# mini_backplane.net
KiCad netlist of a schematic drawn in Altium Designer
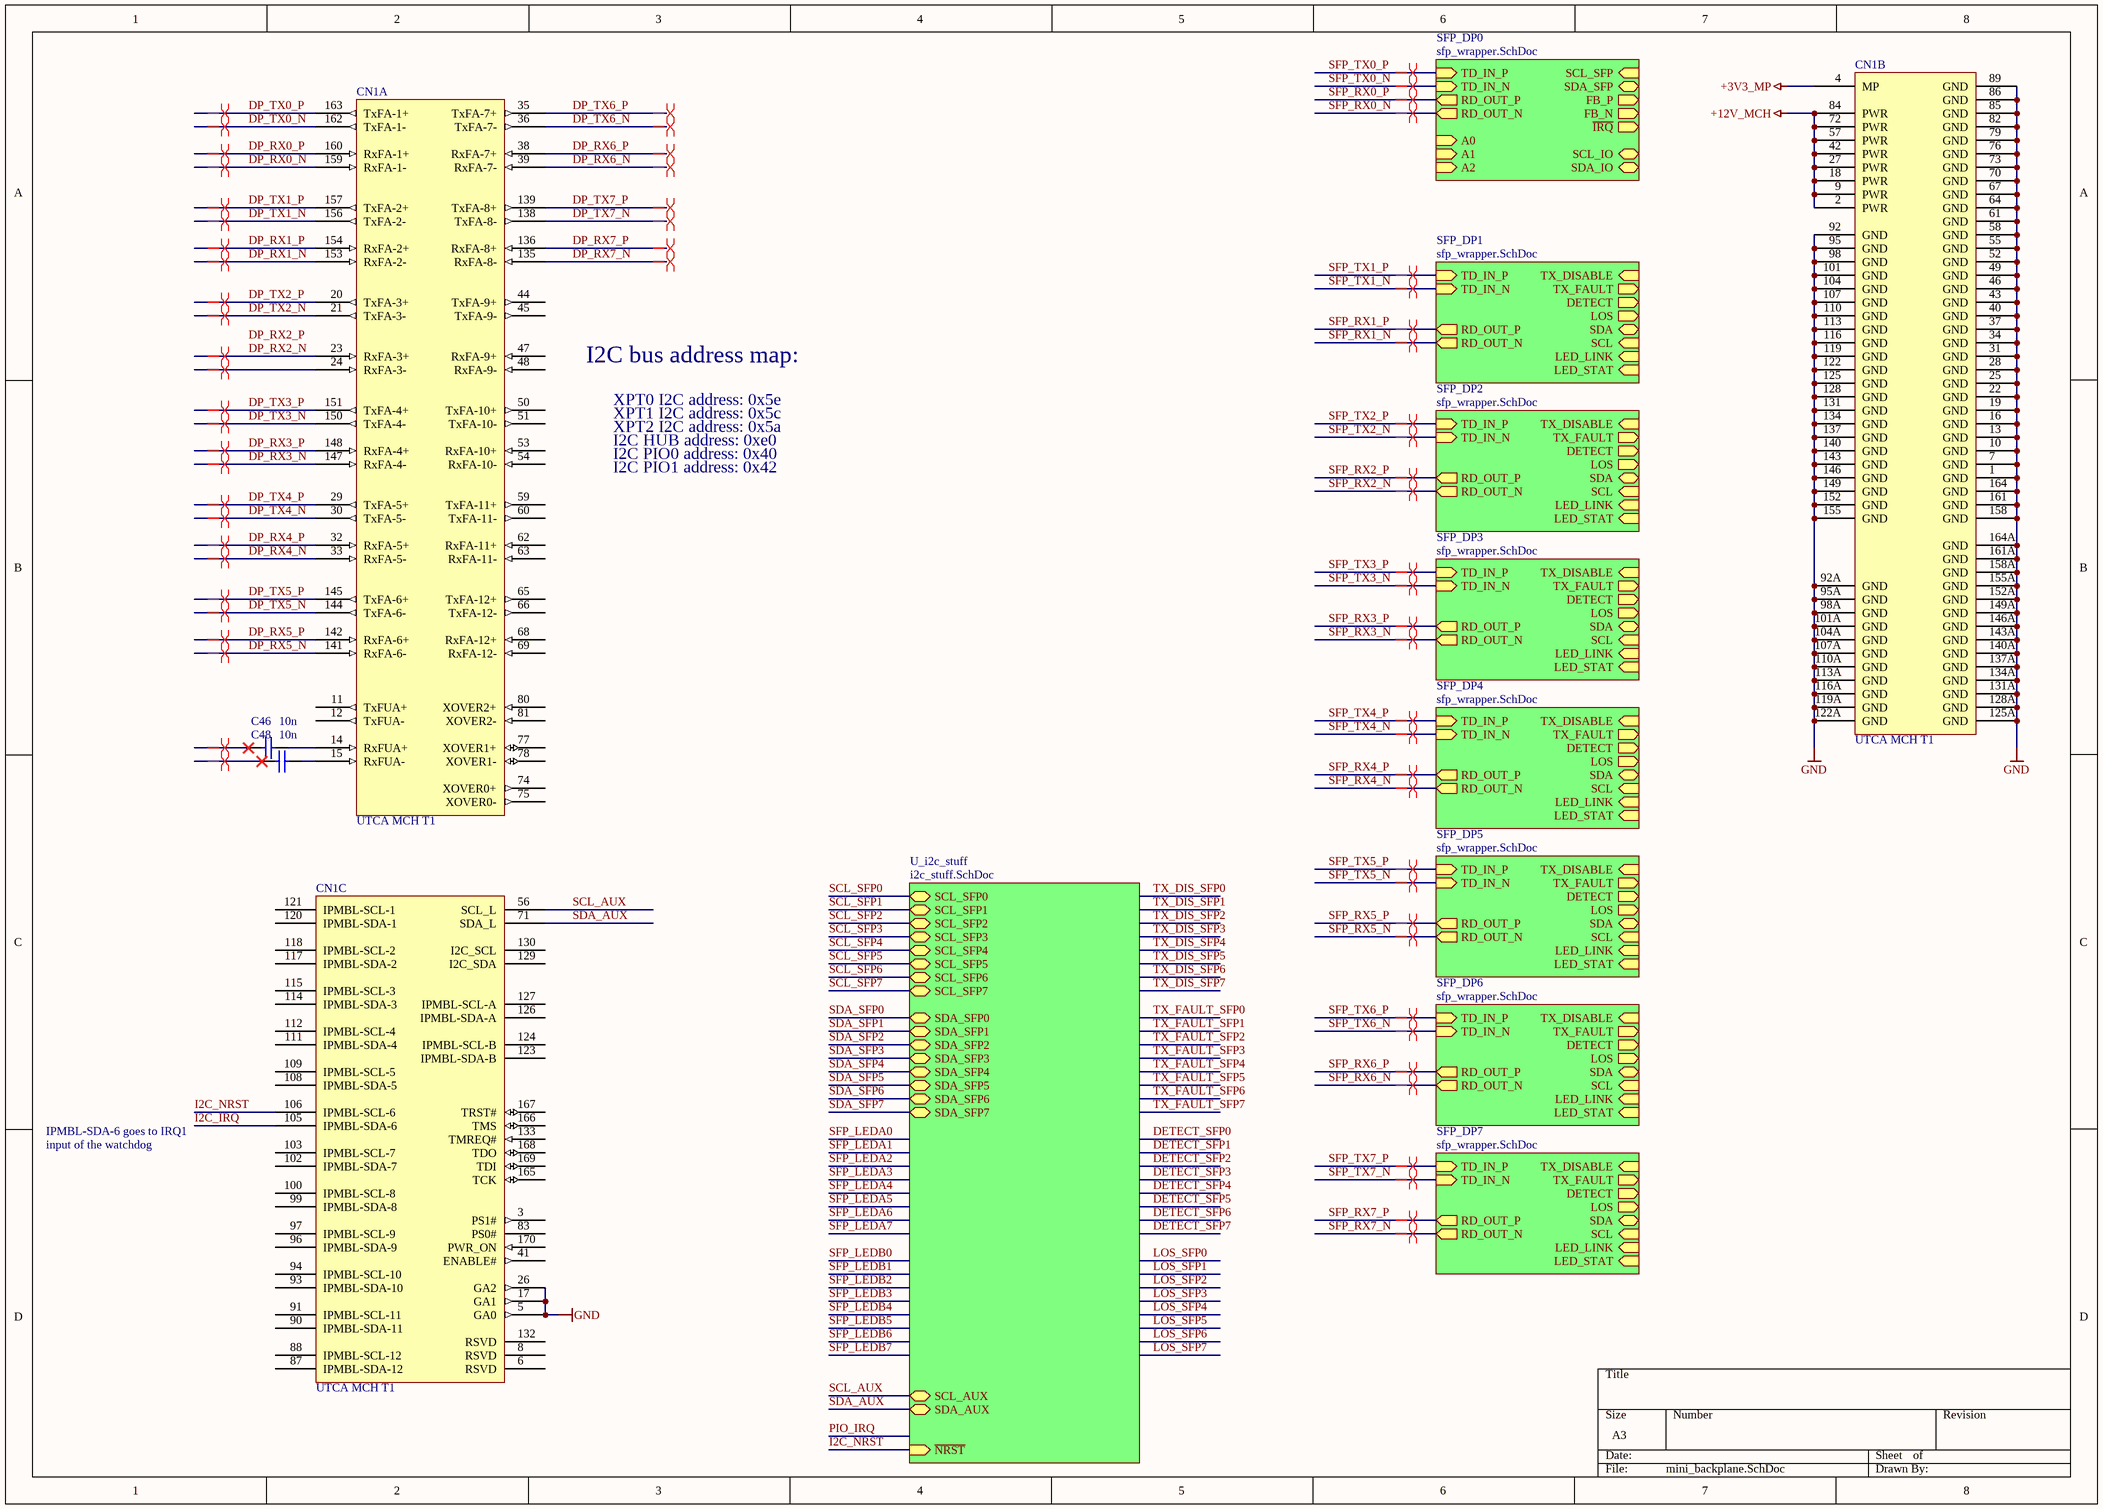
[diagram p0: mini_backplane.SchDoc]

(export (version "E")
  (design (tool "Eeschema 10.0.6"))
  (components
    (comp (ref "C46")
      (value "10n")
      (footprint "CAPC1608X87N")
      (description "Non-polarised capacitor")
      (fields
        (field (name "PART NUMBER") "CC0603_10NF_50V_10%_X7R")
        (field (name "VOLTAGE") "50V")
        (field (name "AUTHOR") "CERN DEM JLC")
      )
      (libsource (lib "Capacitors") (part "Capacitor - non polarized"))
    )
    (comp (ref "C48")
      (value "10n")
      (footprint "CAPC1608X87N")
      (description "Non-polarised capacitor")
      (fields
        (field (name "PART NUMBER") "CC0603_10NF_50V_10%_X7R")
        (field (name "VOLTAGE") "50V")
        (field (name "AUTHOR") "CERN DEM JLC")
      )
      (libsource (lib "Capacitors") (part "Capacitor - non polarized"))
    )
    (comp (ref "CN1")
      (value "UTCA MCH T1")
      (footprint "CON_AMC_MOLEX_75800_00001_REVERSE")
      (description "microTCA MTCA.0  MCH socket (AMC0.0 B+ connector with reversed pins)")
      (libsource (lib "wr_switch") (part "UTCA_MCH_SOCKET"))
    )
  )
  (nets
    (net (code "1") (name "+3V3_MP") (class "Default")
      (node (ref "CN1") (pin "4") (pinfunction "MP_4") (pintype "power_in"))
    )
    (net (code "2") (name "+12V_MCH") (class "Default")
      (node (ref "CN1") (pin "18") (pinfunction "PWR_18") (pintype "power_in"))
      (node (ref "CN1") (pin "2") (pinfunction "PWR_2") (pintype "power_in"))
      (node (ref "CN1") (pin "27") (pinfunction "PWR_27") (pintype "power_in"))
      (node (ref "CN1") (pin "42") (pinfunction "PWR_42") (pintype "power_in"))
      (node (ref "CN1") (pin "57") (pinfunction "PWR_57") (pintype "power_in"))
      (node (ref "CN1") (pin "72") (pinfunction "PWR_72") (pintype "power_in"))
      (node (ref "CN1") (pin "84") (pinfunction "PWR_84") (pintype "power_in"))
      (node (ref "CN1") (pin "9") (pinfunction "PWR_9") (pintype "power_in"))
    )
    (net (code "21") (name "/DP_RX0_N") (class "Default")
      (node (ref "CN1") (pin "159") (pinfunction "RxFA-1-_159") (pintype "input"))
    )
    (net (code "22") (name "/DP_RX0_P") (class "Default")
      (node (ref "CN1") (pin "160") (pinfunction "RxFA-1+_160") (pintype "input"))
    )
    (net (code "23") (name "/DP_RX1_N") (class "Default")
      (node (ref "CN1") (pin "153") (pinfunction "RxFA-2-_153") (pintype "input"))
    )
    (net (code "24") (name "/DP_RX1_P") (class "Default")
      (node (ref "CN1") (pin "154") (pinfunction "RxFA-2+_154") (pintype "input"))
    )
    (net (code "25") (name "/DP_RX2_N") (class "Default")
      (node (ref "CN1") (pin "23") (pinfunction "RxFA-3+_23") (pintype "input"))
    )
    (net (code "27") (name "/DP_RX3_N") (class "Default")
      (node (ref "CN1") (pin "147") (pinfunction "RxFA-4-_147") (pintype "input"))
    )
    (net (code "28") (name "/DP_RX3_P") (class "Default")
      (node (ref "CN1") (pin "148") (pinfunction "RxFA-4+_148") (pintype "input"))
    )
    (net (code "29") (name "/DP_RX4_N") (class "Default")
      (node (ref "CN1") (pin "33") (pinfunction "RxFA-5-_33") (pintype "input"))
    )
    (net (code "30") (name "/DP_RX4_P") (class "Default")
      (node (ref "CN1") (pin "32") (pinfunction "RxFA-5+_32") (pintype "input"))
    )
    (net (code "31") (name "/DP_RX5_N") (class "Default")
      (node (ref "CN1") (pin "141") (pinfunction "RxFA-6-_141") (pintype "input"))
    )
    (net (code "32") (name "/DP_RX5_P") (class "Default")
      (node (ref "CN1") (pin "142") (pinfunction "RxFA-6+_142") (pintype "input"))
    )
    (net (code "33") (name "/DP_RX6_N") (class "Default")
      (node (ref "CN1") (pin "39") (pinfunction "RxFA-7-_39") (pintype "input"))
    )
    (net (code "34") (name "/DP_RX6_P") (class "Default")
      (node (ref "CN1") (pin "38") (pinfunction "RxFA-7+_38") (pintype "input"))
    )
    (net (code "35") (name "/DP_RX7_N") (class "Default")
      (node (ref "CN1") (pin "135") (pinfunction "RxFA-8-_135") (pintype "input"))
    )
    (net (code "36") (name "/DP_RX7_P") (class "Default")
      (node (ref "CN1") (pin "136") (pinfunction "RxFA-8+_136") (pintype "input"))
    )
    (net (code "37") (name "/DP_TX0_N") (class "Default")
      (node (ref "CN1") (pin "162") (pinfunction "TxFA-1-_162") (pintype "output"))
    )
    (net (code "38") (name "/DP_TX0_P") (class "Default")
      (node (ref "CN1") (pin "163") (pinfunction "TxFA-1+_163") (pintype "output"))
    )
    (net (code "39") (name "/DP_TX1_N") (class "Default")
      (node (ref "CN1") (pin "156") (pinfunction "TxFA-2-_156") (pintype "output"))
    )
    (net (code "40") (name "/DP_TX1_P") (class "Default")
      (node (ref "CN1") (pin "157") (pinfunction "TxFA-2+_157") (pintype "output"))
    )
    (net (code "41") (name "/DP_TX2_N") (class "Default")
      (node (ref "CN1") (pin "21") (pinfunction "TxFA-3-_21") (pintype "output"))
    )
    (net (code "42") (name "/DP_TX2_P") (class "Default")
      (node (ref "CN1") (pin "20") (pinfunction "TxFA-3+_20") (pintype "output"))
    )
    (net (code "43") (name "/DP_TX3_N") (class "Default")
      (node (ref "CN1") (pin "150") (pinfunction "TxFA-4-_150") (pintype "output"))
    )
    (net (code "44") (name "/DP_TX3_P") (class "Default")
      (node (ref "CN1") (pin "151") (pinfunction "TxFA-4+_151") (pintype "output"))
    )
    (net (code "45") (name "/DP_TX4_N") (class "Default")
      (node (ref "CN1") (pin "30") (pinfunction "TxFA-5-_30") (pintype "output"))
    )
    (net (code "46") (name "/DP_TX4_P") (class "Default")
      (node (ref "CN1") (pin "29") (pinfunction "TxFA-5+_29") (pintype "output"))
    )
    (net (code "47") (name "/DP_TX5_N") (class "Default")
      (node (ref "CN1") (pin "144") (pinfunction "TxFA-6-_144") (pintype "output"))
    )
    (net (code "48") (name "/DP_TX5_P") (class "Default")
      (node (ref "CN1") (pin "145") (pinfunction "TxFA-6+_145") (pintype "output"))
    )
    (net (code "49") (name "/DP_TX6_N") (class "Default")
      (node (ref "CN1") (pin "36") (pinfunction "TxFA-7-_36") (pintype "output"))
    )
    (net (code "50") (name "/DP_TX6_P") (class "Default")
      (node (ref "CN1") (pin "35") (pinfunction "TxFA-7+_35") (pintype "output"))
    )
    (net (code "51") (name "/DP_TX7_N") (class "Default")
      (node (ref "CN1") (pin "138") (pinfunction "TxFA-8-_138") (pintype "output"))
    )
    (net (code "52") (name "/DP_TX7_P") (class "Default")
      (node (ref "CN1") (pin "139") (pinfunction "TxFA-8+_139") (pintype "output"))
    )
    (net (code "55") (name "/I2C_IRQ") (class "Default")
      (node (ref "CN1") (pin "105") (pinfunction "IPMBL-SDA-6_105") (pintype "open_collector"))
    )
    (net (code "56") (name "/I2C_NRST") (class "Default")
      (node (ref "CN1") (pin "106") (pinfunction "IPMBL-SCL-6_106") (pintype "open_collector"))
    )
    (net (code "94") (name "/SCL_AUX") (class "Default")
      (node (ref "CN1") (pin "56") (pinfunction "SCL_L_56") (pintype "open_collector"))
    )
    (net (code "112") (name "/SDA_AUX") (class "Default")
      (node (ref "CN1") (pin "71") (pinfunction "SDA_L_71") (pintype "open_collector"))
    )
    (net (code "202") (name "GND") (class "Default")
      (node (ref "CN1") (pin "1") (pinfunction "GND_1") (pintype "power_in"))
      (node (ref "CN1") (pin "10") (pinfunction "GND_10") (pintype "power_in"))
      (node (ref "CN1") (pin "101") (pinfunction "GND_101") (pintype "power_in"))
      (node (ref "CN1") (pin "101A") (pinfunction "GND_101A") (pintype "power_in"))
      (node (ref "CN1") (pin "104") (pinfunction "GND_104") (pintype "power_in"))
      (node (ref "CN1") (pin "104A") (pinfunction "GND_104A") (pintype "power_in"))
      (node (ref "CN1") (pin "107") (pinfunction "GND_107") (pintype "power_in"))
      (node (ref "CN1") (pin "107A") (pinfunction "GND_107A") (pintype "power_in"))
      (node (ref "CN1") (pin "110") (pinfunction "GND_110") (pintype "power_in"))
      (node (ref "CN1") (pin "110A") (pinfunction "GND_110A") (pintype "power_in"))
      (node (ref "CN1") (pin "113") (pinfunction "GND_113") (pintype "power_in"))
      (node (ref "CN1") (pin "113A") (pinfunction "GND_113A") (pintype "power_in"))
      (node (ref "CN1") (pin "116") (pinfunction "GND_116") (pintype "power_in"))
      (node (ref "CN1") (pin "116A") (pinfunction "GND_116A") (pintype "power_in"))
      (node (ref "CN1") (pin "119") (pinfunction "GND_119") (pintype "power_in"))
      (node (ref "CN1") (pin "119A") (pinfunction "GND_119A") (pintype "power_in"))
      (node (ref "CN1") (pin "122") (pinfunction "GND_122") (pintype "power_in"))
      (node (ref "CN1") (pin "122A") (pinfunction "GND_122A") (pintype "power_in"))
      (node (ref "CN1") (pin "125") (pinfunction "GND_125") (pintype "power_in"))
      (node (ref "CN1") (pin "125A") (pinfunction "GND_125A") (pintype "power_in"))
      (node (ref "CN1") (pin "128") (pinfunction "GND_128") (pintype "power_in"))
      (node (ref "CN1") (pin "128A") (pinfunction "GND_128A") (pintype "power_in"))
      (node (ref "CN1") (pin "13") (pinfunction "GND_13") (pintype "power_in"))
      (node (ref "CN1") (pin "131") (pinfunction "GND_131") (pintype "power_in"))
      (node (ref "CN1") (pin "131A") (pinfunction "GND_131A") (pintype "power_in"))
      (node (ref "CN1") (pin "134") (pinfunction "GND_134") (pintype "power_in"))
      (node (ref "CN1") (pin "134A") (pinfunction "GND_134A") (pintype "power_in"))
      (node (ref "CN1") (pin "137") (pinfunction "GND_137") (pintype "power_in"))
      (node (ref "CN1") (pin "137A") (pinfunction "GND_137A") (pintype "power_in"))
      (node (ref "CN1") (pin "140") (pinfunction "GND_140") (pintype "power_in"))
      (node (ref "CN1") (pin "140A") (pinfunction "GND_140A") (pintype "power_in"))
      (node (ref "CN1") (pin "143") (pinfunction "GND_143") (pintype "power_in"))
      (node (ref "CN1") (pin "143A") (pinfunction "GND_143A") (pintype "power_in"))
      (node (ref "CN1") (pin "146") (pinfunction "GND_146") (pintype "power_in"))
      (node (ref "CN1") (pin "146A") (pinfunction "GND_146A") (pintype "power_in"))
      (node (ref "CN1") (pin "149") (pinfunction "GND_149") (pintype "power_in"))
      (node (ref "CN1") (pin "149A") (pinfunction "GND_149A") (pintype "power_in"))
      (node (ref "CN1") (pin "152") (pinfunction "GND_152") (pintype "power_in"))
      (node (ref "CN1") (pin "152A") (pinfunction "GND_152A") (pintype "power_in"))
      (node (ref "CN1") (pin "155") (pinfunction "GND_155") (pintype "power_in"))
      (node (ref "CN1") (pin "155A") (pinfunction "GND_155A") (pintype "power_in"))
      (node (ref "CN1") (pin "158") (pinfunction "GND_158") (pintype "power_in"))
      (node (ref "CN1") (pin "158A") (pinfunction "GND_158A") (pintype "power_in"))
      (node (ref "CN1") (pin "16") (pinfunction "GND_16") (pintype "power_in"))
      (node (ref "CN1") (pin "161") (pinfunction "GND_161") (pintype "power_in"))
      (node (ref "CN1") (pin "161A") (pinfunction "GND_161A") (pintype "power_in"))
      (node (ref "CN1") (pin "164") (pinfunction "GND_164") (pintype "power_in"))
      (node (ref "CN1") (pin "164A") (pinfunction "GND_164A") (pintype "power_in"))
      (node (ref "CN1") (pin "17") (pinfunction "GA1_17") (pintype "output"))
      (node (ref "CN1") (pin "19") (pinfunction "GND_19") (pintype "power_in"))
      (node (ref "CN1") (pin "22") (pinfunction "GND_22") (pintype "power_in"))
      (node (ref "CN1") (pin "25") (pinfunction "GND_25") (pintype "power_in"))
      (node (ref "CN1") (pin "26") (pinfunction "GA2_26") (pintype "output"))
      (node (ref "CN1") (pin "28") (pinfunction "GND_28") (pintype "power_in"))
      (node (ref "CN1") (pin "31") (pinfunction "GND_31") (pintype "power_in"))
      (node (ref "CN1") (pin "34") (pinfunction "GND_34") (pintype "power_in"))
      (node (ref "CN1") (pin "37") (pinfunction "GND_37") (pintype "power_in"))
      (node (ref "CN1") (pin "40") (pinfunction "GND_40") (pintype "power_in"))
      (node (ref "CN1") (pin "43") (pinfunction "GND_43") (pintype "power_in"))
      (node (ref "CN1") (pin "46") (pinfunction "GND_46") (pintype "power_in"))
      (node (ref "CN1") (pin "49") (pinfunction "GND_49") (pintype "power_in"))
      (node (ref "CN1") (pin "5") (pinfunction "GA0_5") (pintype "output"))
      (node (ref "CN1") (pin "52") (pinfunction "GND_52") (pintype "power_in"))
      (node (ref "CN1") (pin "55") (pinfunction "GND_55") (pintype "power_in"))
      (node (ref "CN1") (pin "58") (pinfunction "GND_58") (pintype "power_in"))
      (node (ref "CN1") (pin "61") (pinfunction "GND_61") (pintype "power_in"))
      (node (ref "CN1") (pin "64") (pinfunction "GND_64") (pintype "power_in"))
      (node (ref "CN1") (pin "67") (pinfunction "GND_67") (pintype "power_in"))
      (node (ref "CN1") (pin "7") (pinfunction "GND_7") (pintype "power_in"))
      (node (ref "CN1") (pin "70") (pinfunction "GND_70") (pintype "power_in"))
      (node (ref "CN1") (pin "73") (pinfunction "GND_73") (pintype "power_in"))
      (node (ref "CN1") (pin "76") (pinfunction "GND_76") (pintype "power_in"))
      (node (ref "CN1") (pin "79") (pinfunction "GND_79") (pintype "power_in"))
      (node (ref "CN1") (pin "82") (pinfunction "GND_82") (pintype "power_in"))
      (node (ref "CN1") (pin "85") (pinfunction "GND_85") (pintype "power_in"))
      (node (ref "CN1") (pin "86") (pinfunction "GND_86") (pintype "power_in"))
      (node (ref "CN1") (pin "89") (pinfunction "GND_89") (pintype "power_in"))
      (node (ref "CN1") (pin "92") (pinfunction "GND_92") (pintype "power_in"))
      (node (ref "CN1") (pin "92A") (pinfunction "GND_92A") (pintype "power_in"))
      (node (ref "CN1") (pin "95") (pinfunction "GND_95") (pintype "power_in"))
      (node (ref "CN1") (pin "95A") (pinfunction "GND_95A") (pintype "power_in"))
      (node (ref "CN1") (pin "98") (pinfunction "GND_98") (pintype "power_in"))
      (node (ref "CN1") (pin "98A") (pinfunction "GND_98A") (pintype "power_in"))
    )
    (net (code "203") (name "Net-(CN1A-RxFUA+)") (class "Default")
      (node (ref "C46") (pin "2") (pinfunction "2_2") (pintype "passive"))
      (node (ref "CN1") (pin "14") (pinfunction "RxFUA+_14") (pintype "input"))
    )
    (net (code "204") (name "Net-(CN1A-RxFUA-)") (class "Default")
      (node (ref "C48") (pin "2") (pinfunction "2_2") (pintype "passive"))
      (node (ref "CN1") (pin "15") (pinfunction "RxFUA-_15") (pintype "input"))
    )
    (net (code "205") (name "unconnected-(C46-Pad1)") (class "Default")
      (node (ref "C46") (pin "1") (pinfunction "1_1") (pintype "passive+no_connect"))
    )
    (net (code "206") (name "unconnected-(C48-Pad1)") (class "Default")
      (node (ref "C48") (pin "1") (pinfunction "1_1") (pintype "passive+no_connect"))
    )
    (net (code "207") (name "unconnected-(CN1A-RxFA-3--Pad24)") (class "Default")
      (node (ref "CN1") (pin "24") (pinfunction "RxFA-3-_24") (pintype "input"))
    )
    (net (code "208") (name "unconnected-(CN1A-RxFA-9+-Pad47)") (class "Default")
      (node (ref "CN1") (pin "47") (pinfunction "RxFA-9+_47") (pintype "input"))
    )
    (net (code "209") (name "unconnected-(CN1A-RxFA-9--Pad48)") (class "Default")
      (node (ref "CN1") (pin "48") (pinfunction "RxFA-9-_48") (pintype "input"))
    )
    (net (code "210") (name "unconnected-(CN1A-RxFA-10+-Pad53)") (class "Default")
      (node (ref "CN1") (pin "53") (pinfunction "RxFA-10+_53") (pintype "input"))
    )
    (net (code "211") (name "unconnected-(CN1A-RxFA-10--Pad54)") (class "Default")
      (node (ref "CN1") (pin "54") (pinfunction "RxFA-10-_54") (pintype "input"))
    )
    (net (code "212") (name "unconnected-(CN1A-RxFA-11+-Pad62)") (class "Default")
      (node (ref "CN1") (pin "62") (pinfunction "RxFA-11+_62") (pintype "input"))
    )
    (net (code "213") (name "unconnected-(CN1A-RxFA-11--Pad63)") (class "Default")
      (node (ref "CN1") (pin "63") (pinfunction "RxFA-11-_63") (pintype "input"))
    )
    (net (code "214") (name "unconnected-(CN1A-RxFA-12+-Pad68)") (class "Default")
      (node (ref "CN1") (pin "68") (pinfunction "RxFA-12+_68") (pintype "input"))
    )
    (net (code "215") (name "unconnected-(CN1A-RxFA-12--Pad69)") (class "Default")
      (node (ref "CN1") (pin "69") (pinfunction "RxFA-12-_69") (pintype "input"))
    )
    (net (code "216") (name "unconnected-(CN1A-TxFA-9+-Pad44)") (class "Default")
      (node (ref "CN1") (pin "44") (pinfunction "TxFA-9+_44") (pintype "output"))
    )
    (net (code "217") (name "unconnected-(CN1A-TxFA-9--Pad45)") (class "Default")
      (node (ref "CN1") (pin "45") (pinfunction "TxFA-9-_45") (pintype "output"))
    )
    (net (code "218") (name "unconnected-(CN1A-TxFA-10+-Pad50)") (class "Default")
      (node (ref "CN1") (pin "50") (pinfunction "TxFA-10+_50") (pintype "output"))
    )
    (net (code "219") (name "unconnected-(CN1A-TxFA-10--Pad51)") (class "Default")
      (node (ref "CN1") (pin "51") (pinfunction "TxFA-10-_51") (pintype "output"))
    )
    (net (code "220") (name "unconnected-(CN1A-TxFA-11+-Pad59)") (class "Default")
      (node (ref "CN1") (pin "59") (pinfunction "TxFA-11+_59") (pintype "output"))
    )
    (net (code "221") (name "unconnected-(CN1A-TxFA-11--Pad60)") (class "Default")
      (node (ref "CN1") (pin "60") (pinfunction "TxFA-11-_60") (pintype "output"))
    )
    (net (code "222") (name "unconnected-(CN1A-TxFA-12+-Pad65)") (class "Default")
      (node (ref "CN1") (pin "65") (pinfunction "TxFA-12+_65") (pintype "output"))
    )
    (net (code "223") (name "unconnected-(CN1A-TxFA-12--Pad66)") (class "Default")
      (node (ref "CN1") (pin "66") (pinfunction "TxFA-12-_66") (pintype "output"))
    )
    (net (code "224") (name "unconnected-(CN1A-TxFUA+-Pad11)") (class "Default")
      (node (ref "CN1") (pin "11") (pinfunction "TxFUA+_11") (pintype "output"))
    )
    (net (code "225") (name "unconnected-(CN1A-TxFUA--Pad12)") (class "Default")
      (node (ref "CN1") (pin "12") (pinfunction "TxFUA-_12") (pintype "output"))
    )
    (net (code "226") (name "unconnected-(CN1A-XOVER0+-Pad74)") (class "Default")
      (node (ref "CN1") (pin "74") (pinfunction "XOVER0+_74") (pintype "output"))
    )
    (net (code "227") (name "unconnected-(CN1A-XOVER0--Pad75)") (class "Default")
      (node (ref "CN1") (pin "75") (pinfunction "XOVER0-_75") (pintype "output"))
    )
    (net (code "228") (name "unconnected-(CN1A-XOVER1+-Pad77)") (class "Default")
      (node (ref "CN1") (pin "77") (pinfunction "XOVER1+_77") (pintype "bidirectional"))
    )
    (net (code "229") (name "unconnected-(CN1A-XOVER1--Pad78)") (class "Default")
      (node (ref "CN1") (pin "78") (pinfunction "XOVER1-_78") (pintype "bidirectional"))
    )
    (net (code "230") (name "unconnected-(CN1A-XOVER2+-Pad80)") (class "Default")
      (node (ref "CN1") (pin "80") (pinfunction "XOVER2+_80") (pintype "input"))
    )
    (net (code "231") (name "unconnected-(CN1A-XOVER2--Pad81)") (class "Default")
      (node (ref "CN1") (pin "81") (pinfunction "XOVER2-_81") (pintype "input"))
    )
    (net (code "232") (name "unconnected-(CN1C-ENABLE#-Pad41)") (class "Default")
      (node (ref "CN1") (pin "41") (pinfunction "ENABLE#_41") (pintype "output"))
    )
    (net (code "233") (name "unconnected-(CN1C-I2C_SCL-Pad130)") (class "Default")
      (node (ref "CN1") (pin "130") (pinfunction "I2C_SCL_130") (pintype "open_collector"))
    )
    (net (code "234") (name "unconnected-(CN1C-I2C_SDA-Pad129)") (class "Default")
      (node (ref "CN1") (pin "129") (pinfunction "I2C_SDA_129") (pintype "open_collector"))
    )
    (net (code "235") (name "unconnected-(CN1C-IPMBL-SCL-1-Pad121)") (class "Default")
      (node (ref "CN1") (pin "121") (pinfunction "IPMBL-SCL-1_121") (pintype "open_collector"))
    )
    (net (code "236") (name "unconnected-(CN1C-IPMBL-SCL-2-Pad118)") (class "Default")
      (node (ref "CN1") (pin "118") (pinfunction "IPMBL-SCL-2_118") (pintype "open_collector"))
    )
    (net (code "237") (name "unconnected-(CN1C-IPMBL-SCL-3-Pad115)") (class "Default")
      (node (ref "CN1") (pin "115") (pinfunction "IPMBL-SCL-3_115") (pintype "open_collector"))
    )
    (net (code "238") (name "unconnected-(CN1C-IPMBL-SCL-4-Pad112)") (class "Default")
      (node (ref "CN1") (pin "112") (pinfunction "IPMBL-SCL-4_112") (pintype "open_collector"))
    )
    (net (code "239") (name "unconnected-(CN1C-IPMBL-SCL-5-Pad109)") (class "Default")
      (node (ref "CN1") (pin "109") (pinfunction "IPMBL-SCL-5_109") (pintype "open_collector"))
    )
    (net (code "240") (name "unconnected-(CN1C-IPMBL-SCL-7-Pad103)") (class "Default")
      (node (ref "CN1") (pin "103") (pinfunction "IPMBL-SCL-7_103") (pintype "open_collector"))
    )
    (net (code "241") (name "unconnected-(CN1C-IPMBL-SCL-8-Pad100)") (class "Default")
      (node (ref "CN1") (pin "100") (pinfunction "IPMBL-SCL-8_100") (pintype "open_collector"))
    )
    (net (code "242") (name "unconnected-(CN1C-IPMBL-SCL-9-Pad97)") (class "Default")
      (node (ref "CN1") (pin "97") (pinfunction "IPMBL-SCL-9_97") (pintype "open_collector"))
    )
    (net (code "243") (name "unconnected-(CN1C-IPMBL-SCL-10-Pad94)") (class "Default")
      (node (ref "CN1") (pin "94") (pinfunction "IPMBL-SCL-10_94") (pintype "open_collector"))
    )
    (net (code "244") (name "unconnected-(CN1C-IPMBL-SCL-11-Pad91)") (class "Default")
      (node (ref "CN1") (pin "91") (pinfunction "IPMBL-SCL-11_91") (pintype "open_collector"))
    )
    (net (code "245") (name "unconnected-(CN1C-IPMBL-SCL-12-Pad88)") (class "Default")
      (node (ref "CN1") (pin "88") (pinfunction "IPMBL-SCL-12_88") (pintype "open_collector"))
    )
    (net (code "246") (name "unconnected-(CN1C-IPMBL-SCL-A-Pad127)") (class "Default")
      (node (ref "CN1") (pin "127") (pinfunction "IPMBL-SCL-A_127") (pintype "open_collector"))
    )
    (net (code "247") (name "unconnected-(CN1C-IPMBL-SCL-B-Pad124)") (class "Default")
      (node (ref "CN1") (pin "124") (pinfunction "IPMBL-SCL-B_124") (pintype "open_collector"))
    )
    (net (code "248") (name "unconnected-(CN1C-IPMBL-SDA-1-Pad120)") (class "Default")
      (node (ref "CN1") (pin "120") (pinfunction "IPMBL-SDA-1_120") (pintype "open_collector"))
    )
    (net (code "249") (name "unconnected-(CN1C-IPMBL-SDA-2-Pad117)") (class "Default")
      (node (ref "CN1") (pin "117") (pinfunction "IPMBL-SDA-2_117") (pintype "open_collector"))
    )
    (net (code "250") (name "unconnected-(CN1C-IPMBL-SDA-3-Pad114)") (class "Default")
      (node (ref "CN1") (pin "114") (pinfunction "IPMBL-SDA-3_114") (pintype "open_collector"))
    )
    (net (code "251") (name "unconnected-(CN1C-IPMBL-SDA-4-Pad111)") (class "Default")
      (node (ref "CN1") (pin "111") (pinfunction "IPMBL-SDA-4_111") (pintype "open_collector"))
    )
    (net (code "252") (name "unconnected-(CN1C-IPMBL-SDA-5-Pad108)") (class "Default")
      (node (ref "CN1") (pin "108") (pinfunction "IPMBL-SDA-5_108") (pintype "open_collector"))
    )
    (net (code "253") (name "unconnected-(CN1C-IPMBL-SDA-7-Pad102)") (class "Default")
      (node (ref "CN1") (pin "102") (pinfunction "IPMBL-SDA-7_102") (pintype "open_collector"))
    )
    (net (code "254") (name "unconnected-(CN1C-IPMBL-SDA-8-Pad99)") (class "Default")
      (node (ref "CN1") (pin "99") (pinfunction "IPMBL-SDA-8_99") (pintype "open_collector"))
    )
    (net (code "255") (name "unconnected-(CN1C-IPMBL-SDA-9-Pad96)") (class "Default")
      (node (ref "CN1") (pin "96") (pinfunction "IPMBL-SDA-9_96") (pintype "open_collector"))
    )
    (net (code "256") (name "unconnected-(CN1C-IPMBL-SDA-10-Pad93)") (class "Default")
      (node (ref "CN1") (pin "93") (pinfunction "IPMBL-SDA-10_93") (pintype "open_collector"))
    )
    (net (code "257") (name "unconnected-(CN1C-IPMBL-SDA-11-Pad90)") (class "Default")
      (node (ref "CN1") (pin "90") (pinfunction "IPMBL-SDA-11_90") (pintype "open_collector"))
    )
    (net (code "258") (name "unconnected-(CN1C-IPMBL-SDA-12-Pad87)") (class "Default")
      (node (ref "CN1") (pin "87") (pinfunction "IPMBL-SDA-12_87") (pintype "open_collector"))
    )
    (net (code "259") (name "unconnected-(CN1C-IPMBL-SDA-A-Pad126)") (class "Default")
      (node (ref "CN1") (pin "126") (pinfunction "IPMBL-SDA-A_126") (pintype "open_collector"))
    )
    (net (code "260") (name "unconnected-(CN1C-IPMBL-SDA-B-Pad123)") (class "Default")
      (node (ref "CN1") (pin "123") (pinfunction "IPMBL-SDA-B_123") (pintype "open_collector"))
    )
    (net (code "261") (name "unconnected-(CN1C-PS0#-Pad83)") (class "Default")
      (node (ref "CN1") (pin "83") (pinfunction "PS0#_83") (pintype "passive"))
    )
    (net (code "262") (name "unconnected-(CN1C-PS1#-Pad3)") (class "Default")
      (node (ref "CN1") (pin "3") (pinfunction "PS1#_3") (pintype "output"))
    )
    (net (code "263") (name "unconnected-(CN1C-PWR_ON-Pad170)") (class "Default")
      (node (ref "CN1") (pin "170") (pinfunction "PWR_ON_170") (pintype "input"))
    )
    (net (code "264") (name "unconnected-(CN1C-RSVD-Pad6)") (class "Default")
      (node (ref "CN1") (pin "6") (pinfunction "RSVD_6") (pintype "tri_state"))
    )
    (net (code "265") (name "unconnected-(CN1C-RSVD-Pad8)") (class "Default")
      (node (ref "CN1") (pin "8") (pinfunction "RSVD_8") (pintype "tri_state"))
    )
    (net (code "266") (name "unconnected-(CN1C-RSVD-Pad132)") (class "Default")
      (node (ref "CN1") (pin "132") (pinfunction "RSVD_132") (pintype "tri_state"))
    )
    (net (code "267") (name "unconnected-(CN1C-TCK-Pad165)") (class "Default")
      (node (ref "CN1") (pin "165") (pinfunction "TCK_165") (pintype "bidirectional"))
    )
    (net (code "268") (name "unconnected-(CN1C-TDI-Pad169)") (class "Default")
      (node (ref "CN1") (pin "169") (pinfunction "TDI_169") (pintype "bidirectional"))
    )
    (net (code "269") (name "unconnected-(CN1C-TDO-Pad168)") (class "Default")
      (node (ref "CN1") (pin "168") (pinfunction "TDO_168") (pintype "bidirectional"))
    )
    (net (code "270") (name "unconnected-(CN1C-TMREQ#-Pad133)") (class "Default")
      (node (ref "CN1") (pin "133") (pinfunction "TMREQ#_133") (pintype "input"))
    )
    (net (code "271") (name "unconnected-(CN1C-TMS-Pad166)") (class "Default")
      (node (ref "CN1") (pin "166") (pinfunction "TMS_166") (pintype "bidirectional"))
    )
    (net (code "272") (name "unconnected-(CN1C-TRST#-Pad167)") (class "Default")
      (node (ref "CN1") (pin "167") (pinfunction "TRST#_167") (pintype "bidirectional"))
    )
  )
)
